# PCB-wPAWS-0_1.net
KiCad netlist of a schematic drawn in EAGLE
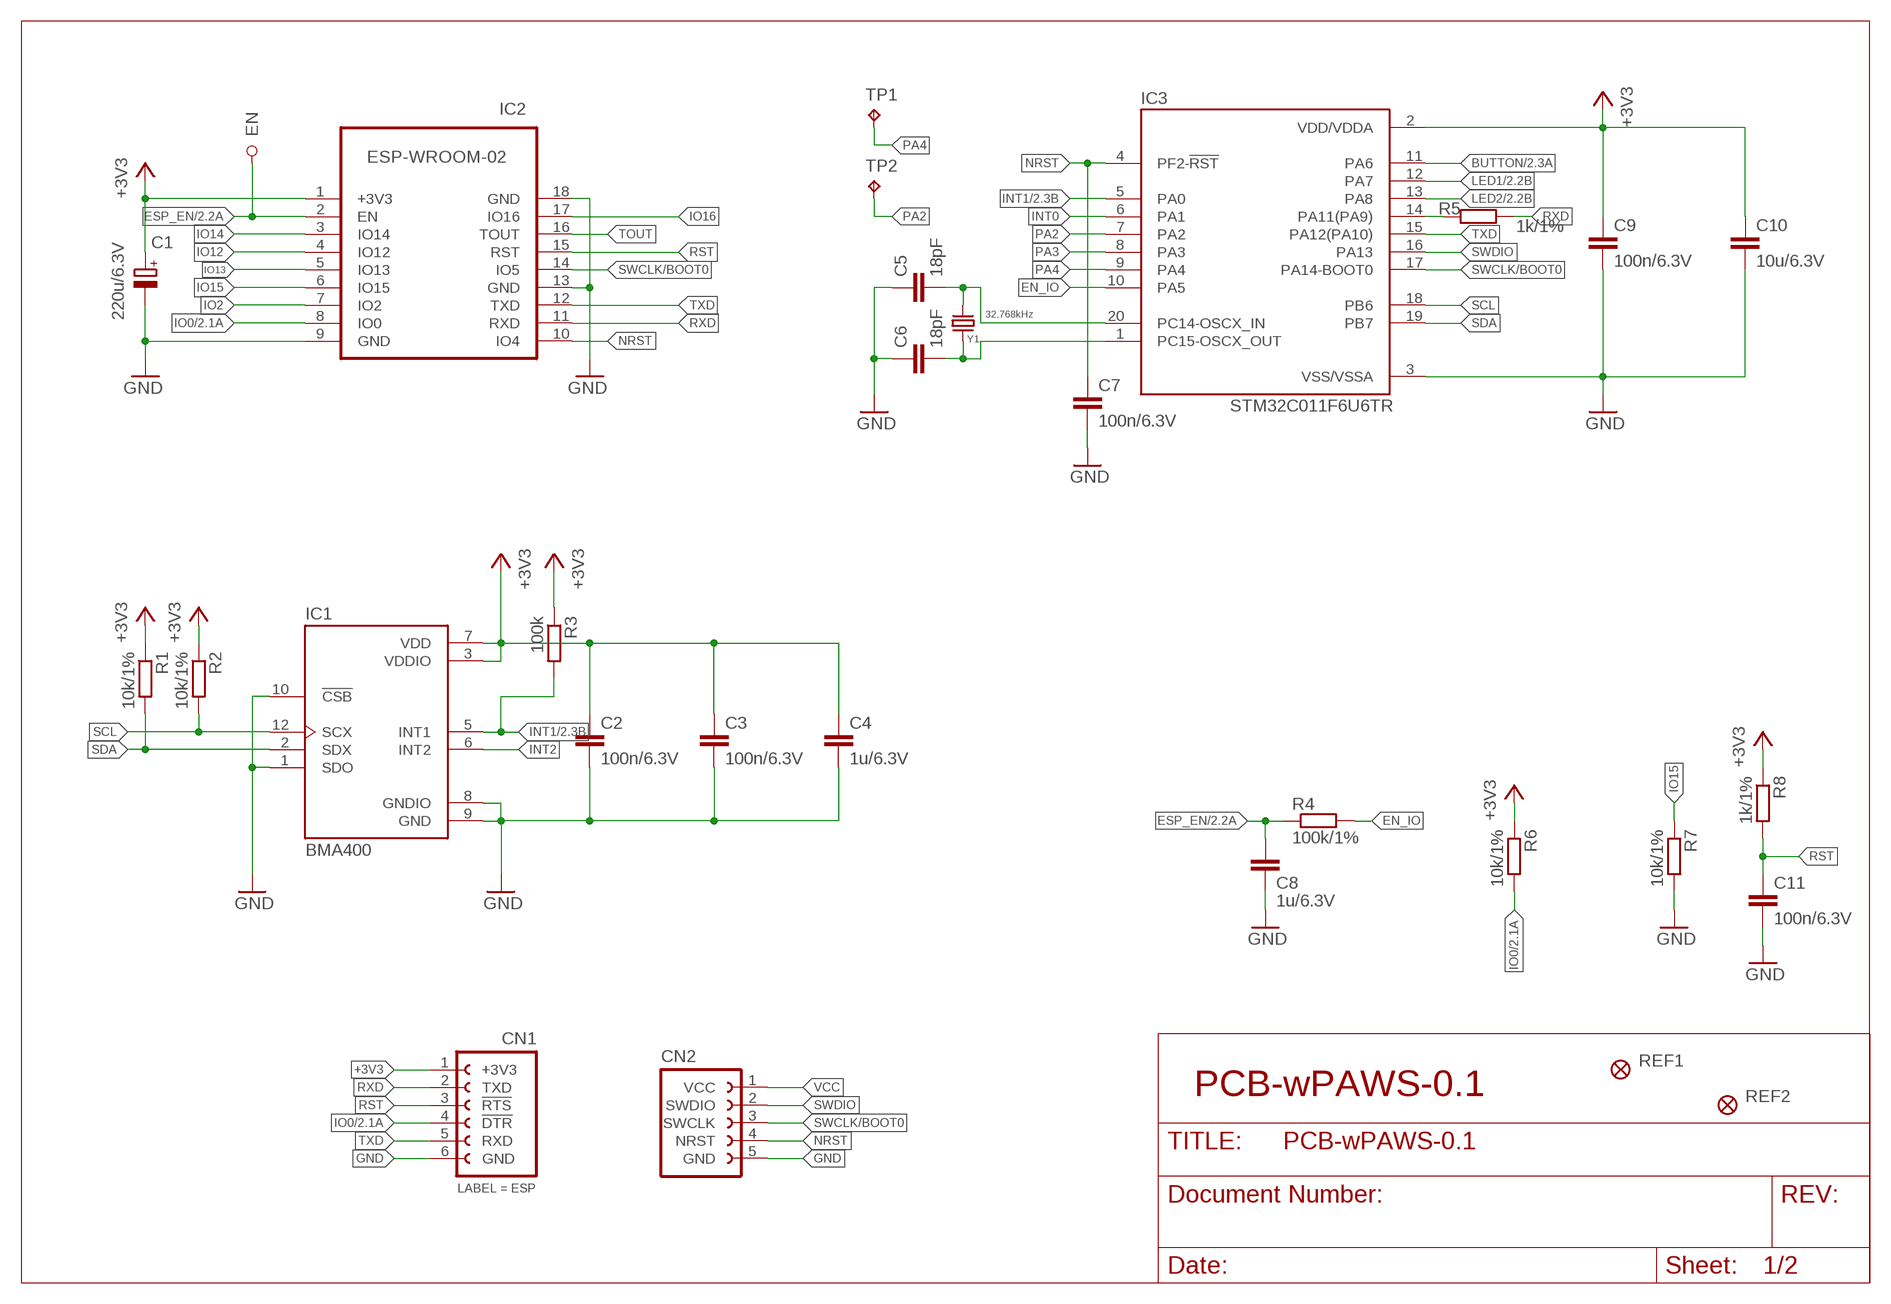
[diagram p0: schematic, sheet 1]
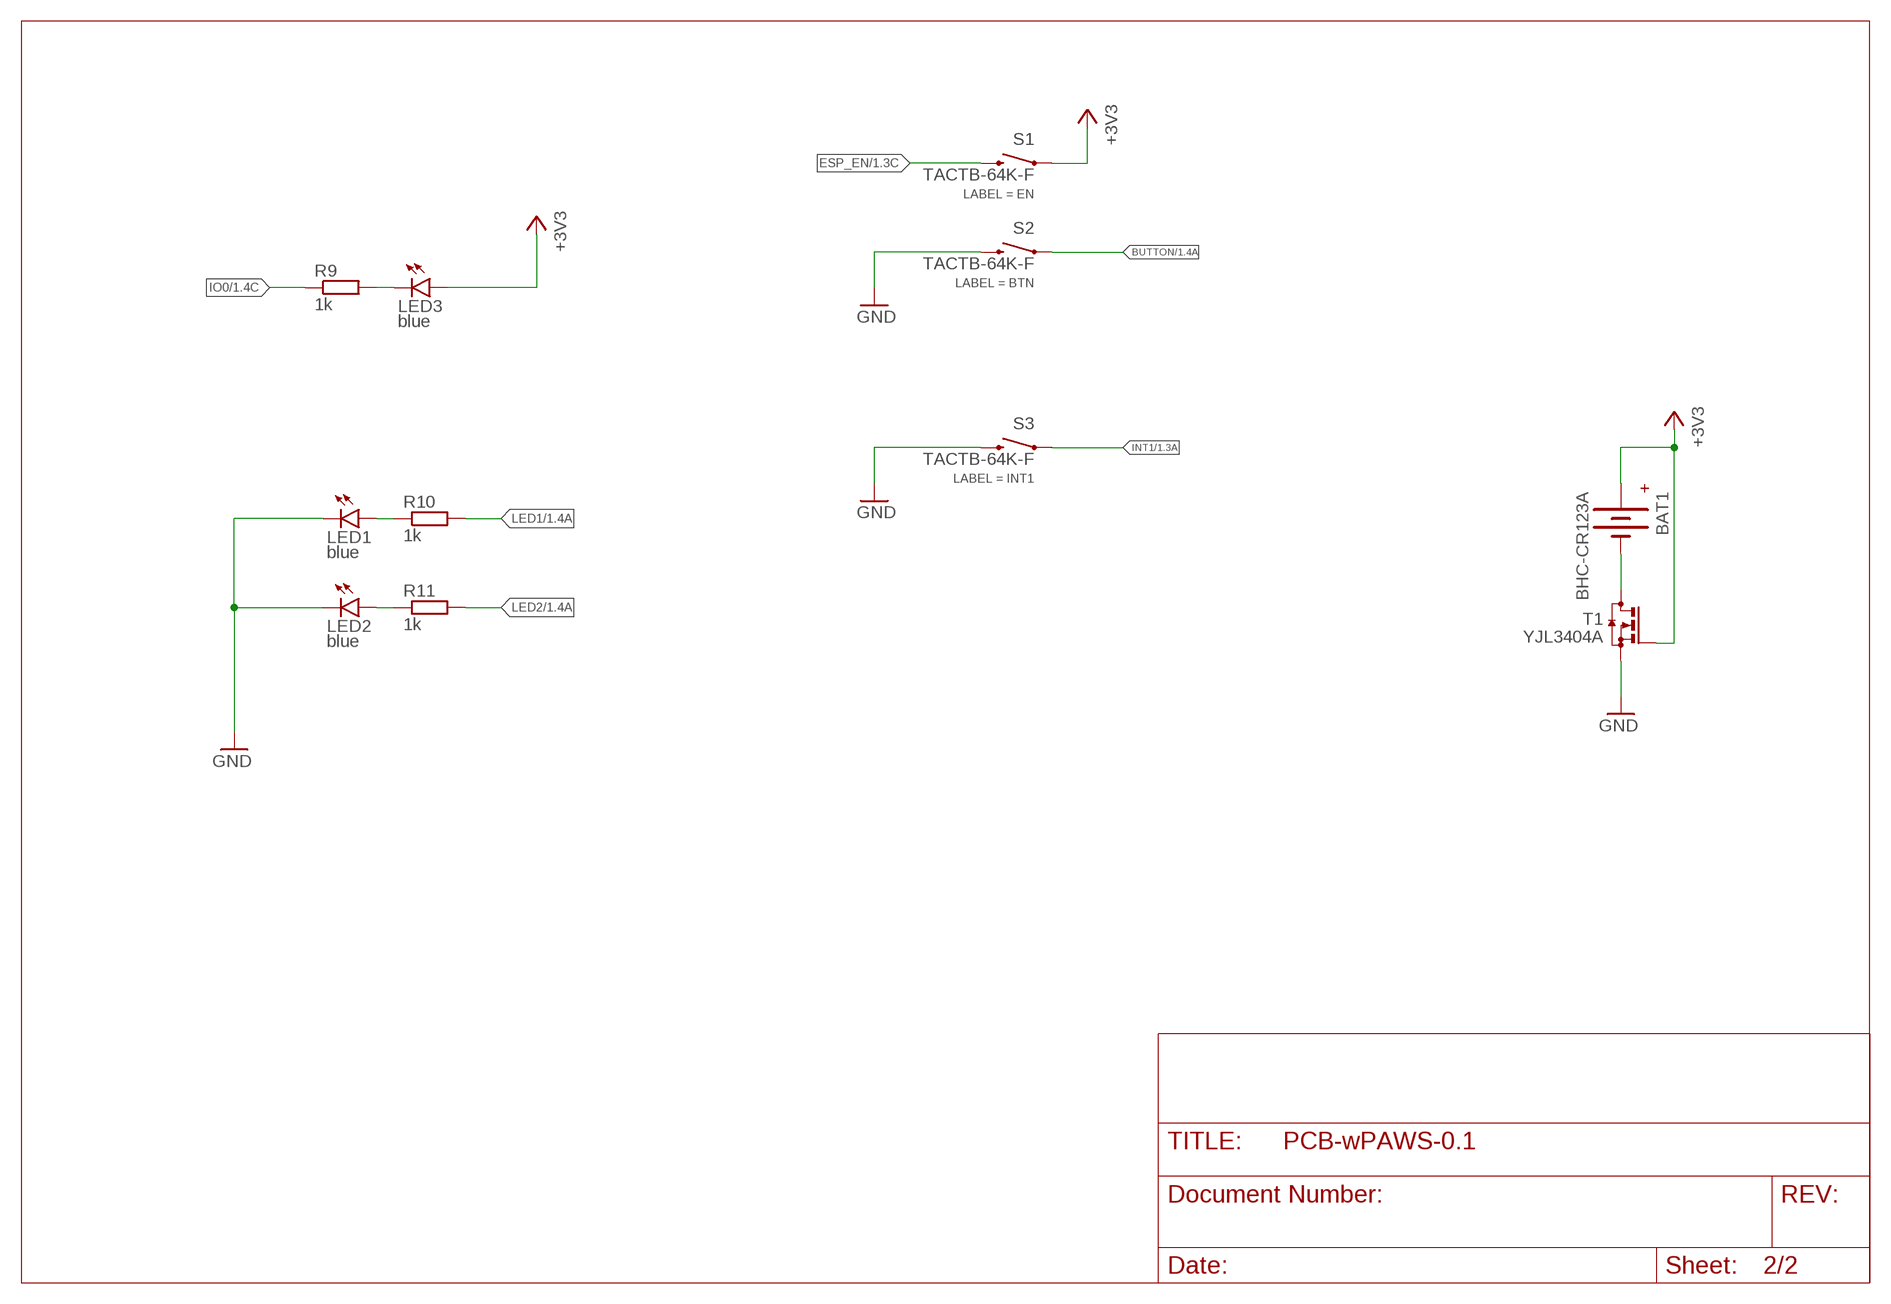
[diagram p1: schematic, sheet 2]

(export (version "E")
  (design (tool "Eeschema 10.0.6"))
  (components
    (comp (ref "C1")
      (value "220u/6.3V")
      (footprint "eagle-import:SMC_C")
      (libsource (lib "eagle-import") (part "CPOL-EUSMCC"))
    )
    (comp (ref "C2")
      (value "100n/6.3V")
      (footprint "eagle-import:C0402")
      (libsource (lib "eagle-import") (part "C0402"))
    )
    (comp (ref "C3")
      (value "100n/6.3V")
      (footprint "eagle-import:C0402")
      (libsource (lib "eagle-import") (part "C0402"))
    )
    (comp (ref "C4")
      (value "1u/6.3V")
      (footprint "eagle-import:C0402")
      (libsource (lib "eagle-import") (part "C0402"))
    )
    (comp (ref "C5")
      (value "18pF")
      (footprint "eagle-import:C0402")
      (libsource (lib "eagle-import") (part "C0402"))
    )
    (comp (ref "C6")
      (value "18pF")
      (footprint "eagle-import:C0402")
      (libsource (lib "eagle-import") (part "C0402"))
    )
    (comp (ref "C7")
      (value "100n/6.3V")
      (footprint "eagle-import:C0402")
      (libsource (lib "eagle-import") (part "C0402"))
    )
    (comp (ref "C8")
      (value "1u/6.3V")
      (footprint "eagle-import:C0402")
      (libsource (lib "eagle-import") (part "C0402"))
    )
    (comp (ref "C9")
      (value "100n/6.3V")
      (footprint "eagle-import:C0402")
      (libsource (lib "eagle-import") (part "C0402"))
    )
    (comp (ref "C10")
      (value "10u/6.3V")
      (footprint "eagle-import:C0402")
      (libsource (lib "eagle-import") (part "C0402"))
    )
    (comp (ref "C11")
      (value "100n/6.3V")
      (footprint "eagle-import:C0402")
      (libsource (lib "eagle-import") (part "C0402"))
    )
    (comp (ref "CN1")
      (value "KOSMOPOLCENTERING-PADS")
      (footprint "eagle-import:6P-2.54-CENTERING-HOLE-PAD")
      (fields (field (name "LABEL") "ESP"))
      (libsource (lib "eagle-import") (part "KOSMOPOLCENTERING-PADS"))
    )
    (comp (ref "CN2")
      (value "SWD2SIDE-CENTRING")
      (footprint "eagle-import:FE05W-SWD-CP")
      (libsource (lib "eagle-import") (part "SWD2SIDE-CENTRING"))
    )
    (comp (ref "IC1")
      (value "BMA400")
      (footprint "eagle-import:XDCR_BMA400")
      (fields (field (name "MF") "Bosch Sensortec"))
      (libsource (lib "eagle-import") (part "BMA400"))
    )
    (comp (ref "IC2")
      (value "ESP-WROOM-02")
      (footprint "eagle-import:MODULE")
      (libsource (lib "eagle-import") (part "ESP-WROOM-02D-32MBIT"))
    )
    (comp (ref "IC3")
      (value "STM32C011F6U6TR")
      (footprint "eagle-import:IC_STM32C011F6U6TR")
      (fields (field (name "MANUFACTURER") "STMicroelectronics"))
      (libsource (lib "eagle-import") (part "STM32C011F6U6TR"))
    )
    (comp (ref "JP1")
      (value "PINHD-1X1")
      (footprint "eagle-import:1X01")
      (fields (field (name "TP_SIGNAL_NAME") "EN"))
      (libsource (lib "eagle-import") (part "PINHD-1X1"))
    )
    (comp (ref "R1")
      (value "10k/1%")
      (footprint "eagle-import:R0402")
      (libsource (lib "eagle-import") (part "blebox-rcl_33525614_R0402"))
    )
    (comp (ref "R2")
      (value "10k/1%")
      (footprint "eagle-import:R0402")
      (libsource (lib "eagle-import") (part "blebox-rcl_33525614_R0402"))
    )
    (comp (ref "R3")
      (value "100k")
      (footprint "eagle-import:R0402")
      (libsource (lib "eagle-import") (part "blebox-rcl_33525614_R0402"))
    )
    (comp (ref "R4")
      (value "100k/1%")
      (footprint "eagle-import:R0402")
      (libsource (lib "eagle-import") (part "blebox-rcl_33525614_R0402"))
    )
    (comp (ref "R5")
      (value "1k/1%")
      (footprint "eagle-import:R0402")
      (libsource (lib "eagle-import") (part "blebox-rcl_33525614_R0402"))
    )
    (comp (ref "R6")
      (value "10k/1%")
      (footprint "eagle-import:R0402")
      (libsource (lib "eagle-import") (part "blebox-rcl_33525614_R0402"))
    )
    (comp (ref "R7")
      (value "10k/1%")
      (footprint "eagle-import:R0402")
      (libsource (lib "eagle-import") (part "blebox-rcl_33525614_R0402"))
    )
    (comp (ref "R8")
      (value "1k/1%")
      (footprint "eagle-import:R0402")
      (libsource (lib "eagle-import") (part "blebox-rcl_33525614_R0402"))
    )
    (comp (ref "REF1")
      (value "FIDUCIAL-CLEAR")
      (footprint "eagle-import:FIDUCIAL-ANDPOL")
      (libsource (lib "eagle-import") (part "FIDUCIAL-CLEAR"))
    )
    (comp (ref "REF2")
      (value "FIDUCIAL-CLEAR")
      (footprint "eagle-import:FIDUCIAL-ANDPOL")
      (libsource (lib "eagle-import") (part "FIDUCIAL-CLEAR"))
    )
    (comp (ref "TP1")
      (value "TPB1,27")
      (footprint "eagle-import:B1,27")
      (libsource (lib "eagle-import") (part "TPB1,27"))
    )
    (comp (ref "TP2")
      (value "TPB1,27")
      (footprint "eagle-import:B1,27")
      (libsource (lib "eagle-import") (part "TPB1,27"))
    )
    (comp (ref "Y1")
      (value "32.768kHz")
      (footprint "eagle-import:WE-XTAL_CFPX-217")
      (fields (field (name "TOLERANCE") "±20ppm"))
      (libsource (lib "eagle-import") (part "WE-XTAL_CFPX-217_830009706"))
    )
    (comp (ref "BAT1")
      (value "BHC-CR123A")
      (footprint "eagle-import:BHC-CR123A")
      (libsource (lib "eagle-import") (part "BATTERYBHC-CR123A"))
    )
    (comp (ref "LED1")
      (value "blue")
      (footprint "eagle-import:CHIPLED_0603")
      (libsource (lib "eagle-import") (part "LEDCHIPLED_0603"))
    )
    (comp (ref "LED2")
      (value "blue")
      (footprint "eagle-import:CHIPLED_0603")
      (libsource (lib "eagle-import") (part "LEDCHIPLED_0603"))
    )
    (comp (ref "LED3")
      (value "blue")
      (footprint "eagle-import:CHIPLED_0603")
      (libsource (lib "eagle-import") (part "LEDCHIPLED_0603"))
    )
    (comp (ref "R9")
      (value "1k")
      (footprint "eagle-import:R0402")
      (libsource (lib "eagle-import") (part "R0402"))
    )
    (comp (ref "R10")
      (value "1k")
      (footprint "eagle-import:R0402")
      (libsource (lib "eagle-import") (part "R0402"))
    )
    (comp (ref "R11")
      (value "1k")
      (footprint "eagle-import:R0402")
      (libsource (lib "eagle-import") (part "R0402"))
    )
    (comp (ref "S1")
      (value "TACTB-64K-F")
      (footprint "eagle-import:TACTILE-SWITCH-SMD")
      (fields (field (name "LABEL") "EN"))
      (libsource (lib "eagle-import") (part "SWITCH-MOMENTARY-2SMD"))
    )
    (comp (ref "S2")
      (value "TACTB-64K-F")
      (footprint "eagle-import:TACTILE-SWITCH-SMD")
      (fields (field (name "LABEL") "BTN"))
      (libsource (lib "eagle-import") (part "SWITCH-MOMENTARY-2SMD"))
    )
    (comp (ref "S3")
      (value "TACTB-64K-F")
      (footprint "eagle-import:TACTILE-SWITCH-SMD")
      (fields (field (name "LABEL") "INT1"))
      (libsource (lib "eagle-import") (part "SWITCH-MOMENTARY-2SMD"))
    )
    (comp (ref "T1")
      (value "YJL3404A")
      (footprint "eagle-import:SOT23-R_INFINEON")
      (libsource (lib "eagle-import") (part "MOSFET-N-SOT23"))
    )
  )
  (nets
    (net (code "1") (name "+3V3") (class "Default")
      (node (ref "BAT1") (pin "VCC") (pinfunction "+_VCC") (pintype "power_in"))
      (node (ref "C1") (pin "+") (pinfunction "+_+") (pintype "passive"))
      (node (ref "C10") (pin "1") (pinfunction "1_1") (pintype "passive"))
      (node (ref "C2") (pin "1") (pinfunction "1_1") (pintype "passive"))
      (node (ref "C3") (pin "1") (pinfunction "1_1") (pintype "passive"))
      (node (ref "C4") (pin "1") (pinfunction "1_1") (pintype "passive"))
      (node (ref "C9") (pin "1") (pinfunction "1_1") (pintype "passive"))
      (node (ref "CN1") (pin "1") (pinfunction "+3V3_1") (pintype "power_in"))
      (node (ref "IC1") (pin "3") (pinfunction "VDDIO_3") (pintype "power_in"))
      (node (ref "IC1") (pin "7") (pinfunction "VDD_7") (pintype "power_in"))
      (node (ref "IC2") (pin "1") (pinfunction "+3V3_1") (pintype "power_in"))
      (node (ref "IC3") (pin "2") (pinfunction "VDD/VDDA_2") (pintype "power_in"))
      (node (ref "LED3") (pin "A") (pinfunction "A_A") (pintype "passive"))
      (node (ref "R1") (pin "1") (pinfunction "1_1") (pintype "passive"))
      (node (ref "R2") (pin "1") (pinfunction "1_1") (pintype "passive"))
      (node (ref "R3") (pin "1") (pinfunction "1_1") (pintype "passive"))
      (node (ref "R6") (pin "1") (pinfunction "1_1") (pintype "passive"))
      (node (ref "R8") (pin "1") (pinfunction "1_1") (pintype "passive"))
      (node (ref "S1") (pin "1") (pinfunction "1_1") (pintype "passive"))
      (node (ref "T1") (pin "1") (pinfunction "G_1") (pintype "passive"))
    )
    (net (code "2") (name "BUTTON") (class "Default")
      (node (ref "IC3") (pin "11") (pinfunction "PA6_11") (pintype "bidirectional"))
      (node (ref "S2") (pin "1") (pinfunction "1_1") (pintype "passive"))
    )
    (net (code "3") (name "EN_IO") (class "Default")
      (node (ref "IC3") (pin "10") (pinfunction "PA5_10") (pintype "bidirectional"))
      (node (ref "R4") (pin "2") (pinfunction "2_2") (pintype "passive"))
    )
    (net (code "4") (name "ESP_EN") (class "Default")
      (node (ref "C8") (pin "1") (pinfunction "1_1") (pintype "passive"))
      (node (ref "IC2") (pin "2") (pinfunction "EN_2") (pintype "bidirectional"))
      (node (ref "JP1") (pin "1") (pinfunction "1_1") (pintype "passive"))
      (node (ref "R4") (pin "1") (pinfunction "1_1") (pintype "passive"))
      (node (ref "S1") (pin "3") (pinfunction "2_3") (pintype "passive"))
    )
    (net (code "5") (name "GND") (class "Default")
      (node (ref "C1") (pin "-") (pinfunction "-_-") (pintype "passive"))
      (node (ref "C10") (pin "2") (pinfunction "2_2") (pintype "passive"))
      (node (ref "C11") (pin "2") (pinfunction "2_2") (pintype "passive"))
      (node (ref "C2") (pin "2") (pinfunction "2_2") (pintype "passive"))
      (node (ref "C3") (pin "2") (pinfunction "2_2") (pintype "passive"))
      (node (ref "C4") (pin "2") (pinfunction "2_2") (pintype "passive"))
      (node (ref "C5") (pin "1") (pinfunction "1_1") (pintype "passive"))
      (node (ref "C6") (pin "1") (pinfunction "1_1") (pintype "passive"))
      (node (ref "C7") (pin "2") (pinfunction "2_2") (pintype "passive"))
      (node (ref "C8") (pin "2") (pinfunction "2_2") (pintype "passive"))
      (node (ref "C9") (pin "2") (pinfunction "2_2") (pintype "passive"))
      (node (ref "CN1") (pin "6") (pinfunction "GND_6") (pintype "power_in"))
      (node (ref "CN2") (pin "5") (pinfunction "GND_5") (pintype "power_in"))
      (node (ref "IC1") (pin "1") (pinfunction "SDO_1") (pintype "bidirectional"))
      (node (ref "IC1") (pin "10") (pinfunction "~{CSB}_10") (pintype "input"))
      (node (ref "IC1") (pin "8") (pinfunction "GNDIO_8") (pintype "power_in"))
      (node (ref "IC1") (pin "9") (pinfunction "GND_9") (pintype "power_in"))
      (node (ref "IC2") (pin "13") (pinfunction "GND_13") (pintype "power_in"))
      (node (ref "IC2") (pin "18") (pinfunction "GND_18") (pintype "power_in"))
      (node (ref "IC2") (pin "9") (pinfunction "GND_9") (pintype "power_in"))
      (node (ref "IC3") (pin "3") (pinfunction "VSS/VSSA_3") (pintype "power_in"))
      (node (ref "LED1") (pin "C") (pinfunction "C_C") (pintype "passive"))
      (node (ref "LED2") (pin "C") (pinfunction "C_C") (pintype "passive"))
      (node (ref "R7") (pin "2") (pinfunction "2_2") (pintype "passive"))
      (node (ref "S2") (pin "3") (pinfunction "2_3") (pintype "passive"))
      (node (ref "S3") (pin "3") (pinfunction "2_3") (pintype "passive"))
      (node (ref "T1") (pin "2") (pinfunction "S_2") (pintype "passive"))
    )
    (net (code "6") (name "INT0") (class "Default")
      (node (ref "IC3") (pin "6") (pinfunction "PA1_6") (pintype "bidirectional"))
    )
    (net (code "7") (name "INT1") (class "Default")
      (node (ref "IC1") (pin "5") (pinfunction "INT1_5") (pintype "bidirectional"))
      (node (ref "IC3") (pin "5") (pinfunction "PA0_5") (pintype "bidirectional"))
      (node (ref "R3") (pin "2") (pinfunction "2_2") (pintype "passive"))
      (node (ref "S3") (pin "1") (pinfunction "1_1") (pintype "passive"))
    )
    (net (code "8") (name "INT2") (class "Default")
      (node (ref "IC1") (pin "6") (pinfunction "INT2_6") (pintype "bidirectional"))
    )
    (net (code "9") (name "IO0") (class "Default")
      (node (ref "CN1") (pin "4") (pinfunction "~{DTR}_4") (pintype "output"))
      (node (ref "IC2") (pin "8") (pinfunction "IO0_8") (pintype "bidirectional"))
      (node (ref "R6") (pin "2") (pinfunction "2_2") (pintype "passive"))
      (node (ref "R9") (pin "1") (pinfunction "1_1") (pintype "passive"))
    )
    (net (code "10") (name "IO2") (class "Default")
      (node (ref "IC2") (pin "7") (pinfunction "IO2_7") (pintype "bidirectional"))
    )
    (net (code "11") (name "IO12") (class "Default")
      (node (ref "IC2") (pin "4") (pinfunction "IO12_4") (pintype "bidirectional"))
    )
    (net (code "12") (name "IO13") (class "Default")
      (node (ref "IC2") (pin "5") (pinfunction "IO13_5") (pintype "bidirectional"))
    )
    (net (code "13") (name "IO14") (class "Default")
      (node (ref "IC2") (pin "3") (pinfunction "IO14_3") (pintype "bidirectional"))
    )
    (net (code "14") (name "IO15") (class "Default")
      (node (ref "IC2") (pin "6") (pinfunction "IO15_6") (pintype "bidirectional"))
      (node (ref "R7") (pin "1") (pinfunction "1_1") (pintype "passive"))
    )
    (net (code "15") (name "IO16") (class "Default")
      (node (ref "IC2") (pin "17") (pinfunction "IO16_17") (pintype "bidirectional"))
    )
    (net (code "16") (name "LED1") (class "Default")
      (node (ref "IC3") (pin "12") (pinfunction "PA7_12") (pintype "bidirectional"))
      (node (ref "R10") (pin "2") (pinfunction "2_2") (pintype "passive"))
    )
    (net (code "17") (name "LED2") (class "Default")
      (node (ref "IC3") (pin "13") (pinfunction "PA8_13") (pintype "bidirectional"))
      (node (ref "R11") (pin "2") (pinfunction "2_2") (pintype "passive"))
    )
    (net (code "18") (name "NRST") (class "Default")
      (node (ref "C7") (pin "1") (pinfunction "1_1") (pintype "passive"))
      (node (ref "CN2") (pin "4") (pinfunction "NRST_4") (pintype "output"))
      (node (ref "IC2") (pin "10") (pinfunction "IO4_10") (pintype "bidirectional"))
      (node (ref "IC3") (pin "4") (pinfunction "PF2-~{RST}_4") (pintype "bidirectional"))
    )
    (net (code "19") (name "Net-(BAT1--)") (class "Default")
      (node (ref "BAT1") (pin "GND") (pinfunction "-_GND") (pintype "power_in"))
      (node (ref "T1") (pin "3") (pinfunction "D_3") (pintype "passive"))
    )
    (net (code "20") (name "Net-(IC3-PA11(PA9))") (class "Default")
      (node (ref "IC3") (pin "14") (pinfunction "PA11(PA9)_14") (pintype "bidirectional"))
      (node (ref "R5") (pin "1") (pinfunction "1_1") (pintype "passive"))
    )
    (net (code "21") (name "Net-(IC3-PC14-OSCX_IN)") (class "Default")
      (node (ref "C5") (pin "2") (pinfunction "2_2") (pintype "passive"))
      (node (ref "IC3") (pin "20") (pinfunction "PC14-OSCX_IN_20") (pintype "bidirectional"))
      (node (ref "Y1") (pin "2") (pinfunction "2_2") (pintype "passive"))
    )
    (net (code "22") (name "Net-(IC3-PC15-OSCX_OUT)") (class "Default")
      (node (ref "C6") (pin "2") (pinfunction "2_2") (pintype "passive"))
      (node (ref "IC3") (pin "1") (pinfunction "PC15-OSCX_OUT_1") (pintype "bidirectional"))
      (node (ref "Y1") (pin "1") (pinfunction "1_1") (pintype "passive"))
    )
    (net (code "23") (name "Net-(LED1-PadA)") (class "Default")
      (node (ref "LED1") (pin "A") (pinfunction "A_A") (pintype "passive"))
      (node (ref "R10") (pin "1") (pinfunction "1_1") (pintype "passive"))
    )
    (net (code "24") (name "Net-(LED2-PadA)") (class "Default")
      (node (ref "LED2") (pin "A") (pinfunction "A_A") (pintype "passive"))
      (node (ref "R11") (pin "1") (pinfunction "1_1") (pintype "passive"))
    )
    (net (code "25") (name "Net-(LED3-PadC)") (class "Default")
      (node (ref "LED3") (pin "C") (pinfunction "C_C") (pintype "passive"))
      (node (ref "R9") (pin "2") (pinfunction "2_2") (pintype "passive"))
    )
    (net (code "26") (name "PA2") (class "Default")
      (node (ref "IC3") (pin "7") (pinfunction "PA2_7") (pintype "bidirectional"))
      (node (ref "TP2") (pin "TP") (pinfunction "TP_TP") (pintype "input"))
    )
    (net (code "27") (name "PA3") (class "Default")
      (node (ref "IC3") (pin "8") (pinfunction "PA3_8") (pintype "bidirectional"))
    )
    (net (code "28") (name "PA4") (class "Default")
      (node (ref "IC3") (pin "9") (pinfunction "PA4_9") (pintype "bidirectional"))
      (node (ref "TP1") (pin "TP") (pinfunction "TP_TP") (pintype "input"))
    )
    (net (code "29") (name "RST") (class "Default")
      (node (ref "C11") (pin "1") (pinfunction "1_1") (pintype "passive"))
      (node (ref "CN1") (pin "3") (pinfunction "~{RTS}_3") (pintype "output"))
      (node (ref "IC2") (pin "15") (pinfunction "RST_15") (pintype "bidirectional"))
      (node (ref "R8") (pin "2") (pinfunction "2_2") (pintype "passive"))
    )
    (net (code "30") (name "RXD") (class "Default")
      (node (ref "CN1") (pin "2") (pinfunction "TXD_2") (pintype "output"))
      (node (ref "IC2") (pin "11") (pinfunction "RXD_11") (pintype "bidirectional"))
      (node (ref "R5") (pin "2") (pinfunction "2_2") (pintype "passive"))
    )
    (net (code "31") (name "SCL") (class "Default")
      (node (ref "IC1") (pin "12") (pinfunction "SCX_12") (pintype "input"))
      (node (ref "IC3") (pin "18") (pinfunction "PB6_18") (pintype "bidirectional"))
      (node (ref "R2") (pin "2") (pinfunction "2_2") (pintype "passive"))
    )
    (net (code "32") (name "SDA") (class "Default")
      (node (ref "IC1") (pin "2") (pinfunction "SDX_2") (pintype "bidirectional"))
      (node (ref "IC3") (pin "19") (pinfunction "PB7_19") (pintype "bidirectional"))
      (node (ref "R1") (pin "2") (pinfunction "2_2") (pintype "passive"))
    )
    (net (code "33") (name "SWCLK{slash}BOOT0") (class "Default")
      (node (ref "CN2") (pin "3") (pinfunction "SWCLK_3") (pintype "output"))
      (node (ref "IC2") (pin "14") (pinfunction "IO5_14") (pintype "bidirectional"))
      (node (ref "IC3") (pin "17") (pinfunction "PA14-BOOT0_17") (pintype "bidirectional"))
    )
    (net (code "34") (name "SWDIO") (class "Default")
      (node (ref "CN2") (pin "2") (pinfunction "SWDIO_2") (pintype "output"))
      (node (ref "IC3") (pin "16") (pinfunction "PA13_16") (pintype "bidirectional"))
    )
    (net (code "35") (name "TOUT") (class "Default")
      (node (ref "IC2") (pin "16") (pinfunction "TOUT_16") (pintype "bidirectional"))
    )
    (net (code "36") (name "TXD") (class "Default")
      (node (ref "CN1") (pin "5") (pinfunction "RXD_5") (pintype "input"))
      (node (ref "IC2") (pin "12") (pinfunction "TXD_12") (pintype "bidirectional"))
      (node (ref "IC3") (pin "15") (pinfunction "PA12(PA10)_15") (pintype "bidirectional"))
    )
    (net (code "37") (name "VCC") (class "Default")
      (node (ref "CN2") (pin "1") (pinfunction "VCC_1") (pintype "power_in"))
    )
  )
)
